# Master.net
KiCad netlist of a schematic drawn in EAGLE
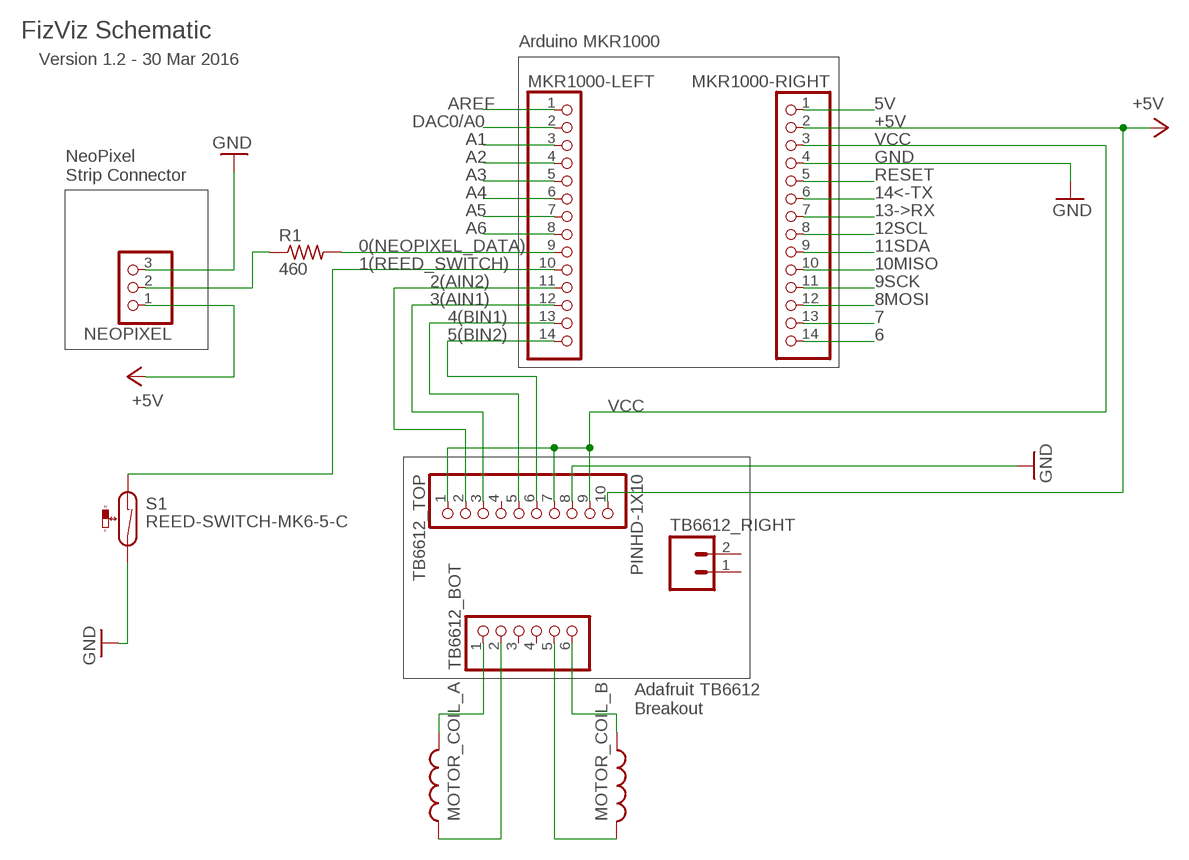
[diagram p0: schematic, sheet 1]

(export (version "E")
  (design (tool "Eeschema 10.0.6"))
  (components
    (comp (ref "MKR1000-LEFT")
      (value "PINHD-1X14")
      (footprint "eagle-import:1X14")
      (libsource (lib "eagle-import") (part "PINHD-1X14"))
    )
    (comp (ref "MKR1000-RIGHT")
      (value "PINHD-1X14")
      (footprint "eagle-import:1X14")
      (libsource (lib "eagle-import") (part "PINHD-1X14"))
    )
    (comp (ref "MOTOR_COIL_A")
      (value "L-US0204/5")
      (footprint "eagle-import:0204_5")
      (libsource (lib "eagle-import") (part "L-US0204/5"))
    )
    (comp (ref "MOTOR_COIL_B")
      (value "L-US0204/5")
      (footprint "eagle-import:0204_5")
      (libsource (lib "eagle-import") (part "L-US0204/5"))
    )
    (comp (ref "NEOPIXEL")
      (value "PINHD-1X3")
      (footprint "eagle-import:1X03")
      (libsource (lib "eagle-import") (part "PINHD-1X3"))
    )
    (comp (ref "R1")
      (value "460")
      (footprint "eagle-import:0204_5")
      (libsource (lib "eagle-import") (part "R-US_0204/5"))
    )
    (comp (ref "S1")
      (value "REED-SWITCH-MK6-5-C")
      (footprint "eagle-import:MK6-5")
      (fields (field (name "MF") "MEDER") (field (name "MPN") "MK6-5-C"))
      (libsource (lib "eagle-import") (part "REED-SWITCH-MK6-5-C"))
    )
    (comp (ref "TB6612_BOT")
      (value "PINHD-1X6B")
      (footprint "eagle-import:1X06-BIG")
      (libsource (lib "eagle-import") (part "PINHD-1X6B"))
    )
    (comp (ref "TB6612_RIGHT")
      (value "M02PTH")
      (footprint "eagle-import:1X02")
      (libsource (lib "eagle-import") (part "M02PTH"))
    )
    (comp (ref "TB6612_TOP")
      (value "PINHD-1X10")
      (footprint "eagle-import:1X10-BIG")
      (libsource (lib "eagle-import") (part "PINHD-1X10"))
    )
  )
  (nets
    (net (code "1") (name "+5V") (class "Default")
      (node (ref "MKR1000-RIGHT") (pin "2") (pinfunction "2_2") (pintype "passive"))
      (node (ref "NEOPIXEL") (pin "1") (pinfunction "1_1") (pintype "passive"))
      (node (ref "TB6612_TOP") (pin "10") (pinfunction "10_10") (pintype "passive"))
    )
    (net (code "2") (name "/0(NEOPIXEL_DATA)") (class "Default")
      (node (ref "MKR1000-LEFT") (pin "9") (pinfunction "9_9") (pintype "passive"))
      (node (ref "R1") (pin "2") (pinfunction "2_2") (pintype "passive"))
    )
    (net (code "3") (name "/1(REED_SWITCH)") (class "Default")
      (node (ref "MKR1000-LEFT") (pin "10") (pinfunction "10_10") (pintype "passive"))
      (node (ref "S1") (pin "1") (pinfunction "1_1") (pintype "passive"))
    )
    (net (code "4") (name "/2(AIN2)") (class "Default")
      (node (ref "MKR1000-LEFT") (pin "11") (pinfunction "11_11") (pintype "passive"))
      (node (ref "TB6612_TOP") (pin "2") (pinfunction "2_2") (pintype "passive"))
    )
    (net (code "5") (name "/3(AIN1)") (class "Default")
      (node (ref "MKR1000-LEFT") (pin "12") (pinfunction "12_12") (pintype "passive"))
      (node (ref "TB6612_TOP") (pin "3") (pinfunction "3_3") (pintype "passive"))
    )
    (net (code "6") (name "/4(BIN1)") (class "Default")
      (node (ref "MKR1000-LEFT") (pin "13") (pinfunction "13_13") (pintype "passive"))
      (node (ref "TB6612_TOP") (pin "5") (pinfunction "5_5") (pintype "passive"))
    )
    (net (code "7") (name "/5(BIN2)") (class "Default")
      (node (ref "MKR1000-LEFT") (pin "14") (pinfunction "14_14") (pintype "passive"))
      (node (ref "TB6612_TOP") (pin "6") (pinfunction "6_6") (pintype "passive"))
    )
    (net (code "8") (name "/5V") (class "Default")
      (node (ref "MKR1000-RIGHT") (pin "1") (pinfunction "1_1") (pintype "passive"))
    )
    (net (code "9") (name "/6") (class "Default")
      (node (ref "MKR1000-RIGHT") (pin "14") (pinfunction "14_14") (pintype "passive"))
    )
    (net (code "10") (name "/7") (class "Default")
      (node (ref "MKR1000-RIGHT") (pin "13") (pinfunction "13_13") (pintype "passive"))
    )
    (net (code "11") (name "/8MOSI") (class "Default")
      (node (ref "MKR1000-RIGHT") (pin "12") (pinfunction "12_12") (pintype "passive"))
    )
    (net (code "12") (name "/9SCK") (class "Default")
      (node (ref "MKR1000-RIGHT") (pin "11") (pinfunction "11_11") (pintype "passive"))
    )
    (net (code "13") (name "/10MISO") (class "Default")
      (node (ref "MKR1000-RIGHT") (pin "10") (pinfunction "10_10") (pintype "passive"))
    )
    (net (code "14") (name "/11SDA") (class "Default")
      (node (ref "MKR1000-RIGHT") (pin "9") (pinfunction "9_9") (pintype "passive"))
    )
    (net (code "15") (name "/12SCL") (class "Default")
      (node (ref "MKR1000-RIGHT") (pin "8") (pinfunction "8_8") (pintype "passive"))
    )
    (net (code "16") (name "/13->RX") (class "Default")
      (node (ref "MKR1000-RIGHT") (pin "7") (pinfunction "7_7") (pintype "passive"))
    )
    (net (code "17") (name "/14<-TX") (class "Default")
      (node (ref "MKR1000-RIGHT") (pin "6") (pinfunction "6_6") (pintype "passive"))
    )
    (net (code "18") (name "/A1") (class "Default")
      (node (ref "MKR1000-LEFT") (pin "3") (pinfunction "3_3") (pintype "passive"))
    )
    (net (code "19") (name "/A2") (class "Default")
      (node (ref "MKR1000-LEFT") (pin "4") (pinfunction "4_4") (pintype "passive"))
    )
    (net (code "20") (name "/A3") (class "Default")
      (node (ref "MKR1000-LEFT") (pin "5") (pinfunction "5_5") (pintype "passive"))
    )
    (net (code "21") (name "/A4") (class "Default")
      (node (ref "MKR1000-LEFT") (pin "6") (pinfunction "6_6") (pintype "passive"))
    )
    (net (code "22") (name "/A5") (class "Default")
      (node (ref "MKR1000-LEFT") (pin "7") (pinfunction "7_7") (pintype "passive"))
    )
    (net (code "23") (name "/A6") (class "Default")
      (node (ref "MKR1000-LEFT") (pin "8") (pinfunction "8_8") (pintype "passive"))
    )
    (net (code "24") (name "/AREF") (class "Default")
      (node (ref "MKR1000-LEFT") (pin "1") (pinfunction "1_1") (pintype "passive"))
    )
    (net (code "25") (name "/DAC0{slash}A0") (class "Default")
      (node (ref "MKR1000-LEFT") (pin "2") (pinfunction "2_2") (pintype "passive"))
    )
    (net (code "26") (name "/RESET") (class "Default")
      (node (ref "MKR1000-RIGHT") (pin "5") (pinfunction "5_5") (pintype "passive"))
    )
    (net (code "27") (name "/VCC") (class "Default")
      (node (ref "MKR1000-RIGHT") (pin "3") (pinfunction "3_3") (pintype "passive"))
      (node (ref "TB6612_TOP") (pin "1") (pinfunction "1_1") (pintype "passive"))
      (node (ref "TB6612_TOP") (pin "7") (pinfunction "7_7") (pintype "passive"))
      (node (ref "TB6612_TOP") (pin "9") (pinfunction "9_9") (pintype "passive"))
    )
    (net (code "28") (name "GND") (class "Default")
      (node (ref "MKR1000-RIGHT") (pin "4") (pinfunction "4_4") (pintype "passive"))
      (node (ref "NEOPIXEL") (pin "3") (pinfunction "3_3") (pintype "passive"))
      (node (ref "S1") (pin "2") (pinfunction "2_2") (pintype "passive"))
      (node (ref "TB6612_TOP") (pin "8") (pinfunction "8_8") (pintype "passive"))
    )
    (net (code "29") (name "Net-(MOTOR_COIL_A-Pad1)") (class "Default")
      (node (ref "MOTOR_COIL_A") (pin "1") (pinfunction "1_1") (pintype "passive"))
      (node (ref "TB6612_BOT") (pin "1") (pinfunction "1_1") (pintype "passive"))
    )
    (net (code "30") (name "Net-(MOTOR_COIL_A-Pad2)") (class "Default")
      (node (ref "MOTOR_COIL_A") (pin "2") (pinfunction "2_2") (pintype "passive"))
      (node (ref "TB6612_BOT") (pin "2") (pinfunction "2_2") (pintype "passive"))
    )
    (net (code "31") (name "Net-(MOTOR_COIL_B-Pad1)") (class "Default")
      (node (ref "MOTOR_COIL_B") (pin "1") (pinfunction "1_1") (pintype "passive"))
      (node (ref "TB6612_BOT") (pin "6") (pinfunction "6_6") (pintype "passive"))
    )
    (net (code "32") (name "Net-(MOTOR_COIL_B-Pad2)") (class "Default")
      (node (ref "MOTOR_COIL_B") (pin "2") (pinfunction "2_2") (pintype "passive"))
      (node (ref "TB6612_BOT") (pin "5") (pinfunction "5_5") (pintype "passive"))
    )
    (net (code "33") (name "Net-(NEOPIXEL-Pad2)") (class "Default")
      (node (ref "NEOPIXEL") (pin "2") (pinfunction "2_2") (pintype "passive"))
      (node (ref "R1") (pin "1") (pinfunction "1_1") (pintype "passive"))
    )
    (net (code "34") (name "unconnected-(TB6612_BOT-Pad3)") (class "Default")
      (node (ref "TB6612_BOT") (pin "3") (pinfunction "3_3") (pintype "passive"))
    )
    (net (code "35") (name "unconnected-(TB6612_BOT-Pad4)") (class "Default")
      (node (ref "TB6612_BOT") (pin "4") (pinfunction "4_4") (pintype "passive"))
    )
    (net (code "36") (name "unconnected-(TB6612_RIGHT-Pad1)") (class "Default")
      (node (ref "TB6612_RIGHT") (pin "1") (pinfunction "1_1") (pintype "passive"))
    )
    (net (code "37") (name "unconnected-(TB6612_RIGHT-Pad2)") (class "Default")
      (node (ref "TB6612_RIGHT") (pin "2") (pinfunction "2_2") (pintype "passive"))
    )
    (net (code "38") (name "unconnected-(TB6612_TOP-Pad4)") (class "Default")
      (node (ref "TB6612_TOP") (pin "4") (pinfunction "4_4") (pintype "passive"))
    )
  )
)
